# PWM_CONTROLLER.net
KiCad netlist of a schematic drawn in EasyEDA
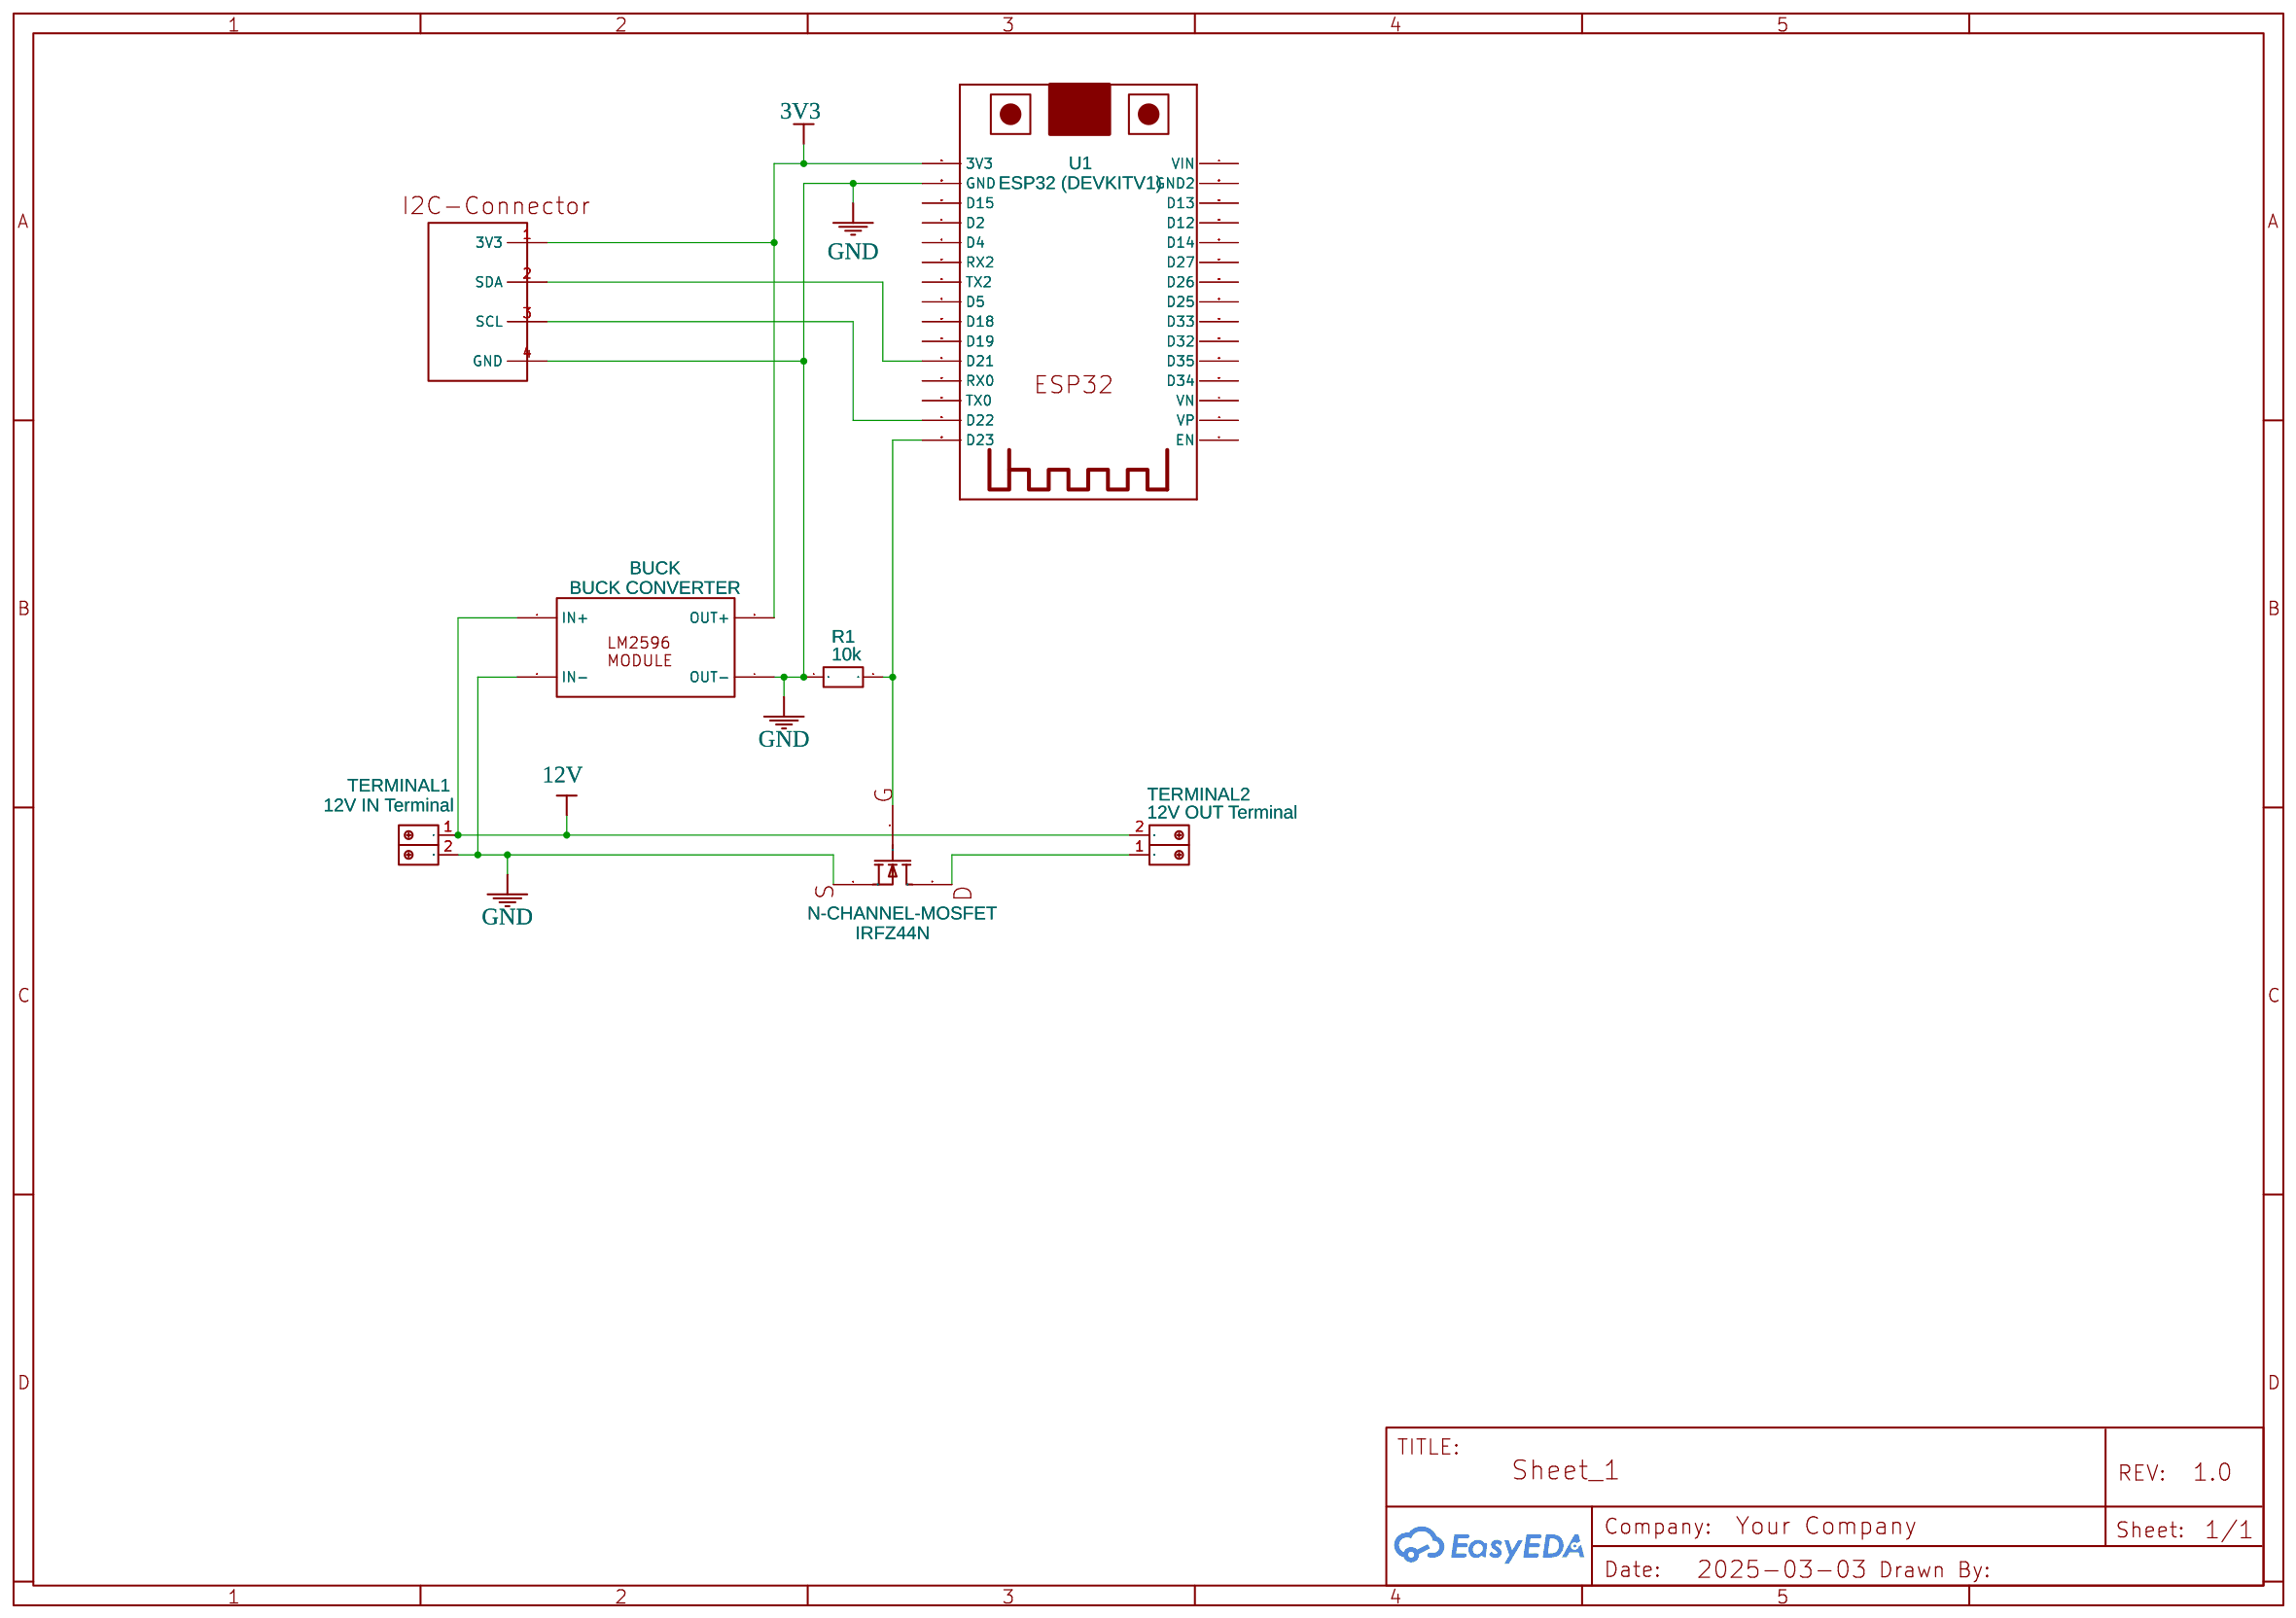
[diagram p0: schematic sheet]

(export (version "E")
  (design (tool "Eeschema 10.0.6"))
  (components
    (comp (ref "BUCK")
      (value "BUCK CONVERTER")
      (fields (field (name "Manufacturer Part") "LM2596-MODULE"))
      (libsource (lib "") (part "LM2596 MODULE - BUCK CONVERTER"))
    )
    (comp (ref "I2C-CONNECTOR") (value "I2C KEYAD (4 PIN)") (libsource (lib "") (part "I2C KEYAD (4 PIN)")))
    (comp (ref "N-CHANNEL-MOSFET") (value "IRFZ44N") (libsource (lib "") (part "MOSFET IRFZ44N")))
    (comp (ref "R1") (value "10k") (libsource (lib "") (part "R_0603_EU")))
    (comp (ref "TERMINAL1")
      (value "12V IN Terminal")
      (fields (field (name "Manufacturer Part") "Screw terminal 2p"))
      (libsource (lib "") (part "Screw terminal 2p_1"))
    )
    (comp (ref "TERMINAL2")
      (value "12V OUT Terminal")
      (fields (field (name "Manufacturer Part") "Screw terminal 2p"))
      (libsource (lib "") (part "Screw terminal 2p"))
    )
    (comp (ref "U1") (value "ESP32 (DEVKITV1)") (libsource (lib "") (part "ESP32-DEVKIT-V1-30PIN")))
  )
  (nets
    (net (code "1") (name "3V3") (class "Default")
      (node (ref "BUCK") (pin "3") (pinfunction "OUT+_3") (pintype "unspecified"))
      (node (ref "I2C-CONNECTOR") (pin "1") (pinfunction "3V3_1") (pintype "unspecified"))
      (node (ref "U1") (pin "3V3") (pinfunction "3V3_3V3") (pintype "unspecified"))
    )
    (net (code "2") (name "12V") (class "Default")
      (node (ref "BUCK") (pin "1") (pinfunction "IN+_1") (pintype "unspecified"))
      (node (ref "TERMINAL1") (pin "1") (pinfunction "1_1") (pintype "unspecified"))
      (node (ref "TERMINAL2") (pin "2") (pinfunction "2_2") (pintype "unspecified"))
    )
    (net (code "3") (name "GND") (class "Default")
      (node (ref "BUCK") (pin "2") (pinfunction "IN-_2") (pintype "unspecified"))
      (node (ref "BUCK") (pin "4") (pinfunction "OUT-_4") (pintype "unspecified"))
      (node (ref "I2C-CONNECTOR") (pin "4") (pinfunction "GND_4") (pintype "unspecified"))
      (node (ref "N-CHANNEL-MOSFET") (pin "3") (pinfunction "S_3") (pintype "unspecified"))
      (node (ref "R1") (pin "1") (pinfunction "1_1") (pintype "unspecified"))
      (node (ref "TERMINAL1") (pin "2") (pinfunction "2_2") (pintype "unspecified"))
      (node (ref "U1") (pin "GND") (pinfunction "GND_GND") (pintype "unspecified"))
    )
    (net (code "4") (name "Net-(I2C-CONNECTOR-SCL)") (class "Default")
      (node (ref "I2C-CONNECTOR") (pin "3") (pinfunction "SCL_3") (pintype "unspecified"))
      (node (ref "U1") (pin "D22") (pinfunction "D22_D22") (pintype "unspecified"))
    )
    (net (code "5") (name "Net-(I2C-CONNECTOR-SDA)") (class "Default")
      (node (ref "I2C-CONNECTOR") (pin "2") (pinfunction "SDA_2") (pintype "unspecified"))
      (node (ref "U1") (pin "D21") (pinfunction "D21_D21") (pintype "unspecified"))
    )
    (net (code "6") (name "Net-(N-CHANNEL-MOSFET-D)") (class "Default")
      (node (ref "N-CHANNEL-MOSFET") (pin "2") (pinfunction "D_2") (pintype "unspecified"))
      (node (ref "TERMINAL2") (pin "1") (pinfunction "1_1") (pintype "unspecified"))
    )
    (net (code "7") (name "Net-(N-CHANNEL-MOSFET-G)") (class "Default")
      (node (ref "N-CHANNEL-MOSFET") (pin "1") (pinfunction "G_1") (pintype "unspecified"))
      (node (ref "R1") (pin "2") (pinfunction "2_2") (pintype "unspecified"))
      (node (ref "U1") (pin "D23") (pinfunction "D23_D23") (pintype "unspecified"))
    )
    (net (code "8") (name "unconnected-(U1-PadD2)") (class "Default")
      (node (ref "U1") (pin "D2") (pinfunction "D2_D2") (pintype "unspecified"))
    )
    (net (code "9") (name "unconnected-(U1-PadD4)") (class "Default")
      (node (ref "U1") (pin "D4") (pinfunction "D4_D4") (pintype "unspecified"))
    )
    (net (code "10") (name "unconnected-(U1-PadD5)") (class "Default")
      (node (ref "U1") (pin "D5") (pinfunction "D5_D5") (pintype "unspecified"))
    )
    (net (code "11") (name "unconnected-(U1-PadD12)") (class "Default")
      (node (ref "U1") (pin "D12") (pinfunction "D12_D12") (pintype "unspecified"))
    )
    (net (code "12") (name "unconnected-(U1-PadD13)") (class "Default")
      (node (ref "U1") (pin "D13") (pinfunction "D13_D13") (pintype "unspecified"))
    )
    (net (code "13") (name "unconnected-(U1-PadD14)") (class "Default")
      (node (ref "U1") (pin "D14") (pinfunction "D14_D14") (pintype "unspecified"))
    )
    (net (code "14") (name "unconnected-(U1-PadD15)") (class "Default")
      (node (ref "U1") (pin "D15") (pinfunction "D15_D15") (pintype "unspecified"))
    )
    (net (code "15") (name "unconnected-(U1-PadD18)") (class "Default")
      (node (ref "U1") (pin "D18") (pinfunction "D18_D18") (pintype "unspecified"))
    )
    (net (code "16") (name "unconnected-(U1-PadD19)") (class "Default")
      (node (ref "U1") (pin "D19") (pinfunction "D19_D19") (pintype "unspecified"))
    )
    (net (code "17") (name "unconnected-(U1-PadD25)") (class "Default")
      (node (ref "U1") (pin "D25") (pinfunction "D25_D25") (pintype "unspecified"))
    )
    (net (code "18") (name "unconnected-(U1-PadD26)") (class "Default")
      (node (ref "U1") (pin "D26") (pinfunction "D26_D26") (pintype "unspecified"))
    )
    (net (code "19") (name "unconnected-(U1-PadD27)") (class "Default")
      (node (ref "U1") (pin "D27") (pinfunction "D27_D27") (pintype "unspecified"))
    )
    (net (code "20") (name "unconnected-(U1-PadD32)") (class "Default")
      (node (ref "U1") (pin "D32") (pinfunction "D32_D32") (pintype "unspecified"))
    )
    (net (code "21") (name "unconnected-(U1-PadD33)") (class "Default")
      (node (ref "U1") (pin "D33") (pinfunction "D33_D33") (pintype "unspecified"))
    )
    (net (code "22") (name "unconnected-(U1-PadD34)") (class "Default")
      (node (ref "U1") (pin "D34") (pinfunction "D34_D34") (pintype "unspecified"))
    )
    (net (code "23") (name "unconnected-(U1-PadD35)") (class "Default")
      (node (ref "U1") (pin "D35") (pinfunction "D35_D35") (pintype "unspecified"))
    )
    (net (code "24") (name "unconnected-(U1-PadEN)") (class "Default")
      (node (ref "U1") (pin "EN") (pinfunction "EN_EN") (pintype "unspecified"))
    )
    (net (code "25") (name "unconnected-(U1-PadGND2)") (class "Default")
      (node (ref "U1") (pin "GND2") (pinfunction "GND2_GND2") (pintype "unspecified"))
    )
    (net (code "26") (name "unconnected-(U1-PadRX0)") (class "Default")
      (node (ref "U1") (pin "RX0") (pinfunction "RX0_RX0") (pintype "unspecified"))
    )
    (net (code "27") (name "unconnected-(U1-PadRX2)") (class "Default")
      (node (ref "U1") (pin "RX2") (pinfunction "RX2_RX2") (pintype "unspecified"))
    )
    (net (code "28") (name "unconnected-(U1-PadTX0)") (class "Default")
      (node (ref "U1") (pin "TX0") (pinfunction "TX0_TX0") (pintype "unspecified"))
    )
    (net (code "29") (name "unconnected-(U1-PadTX2)") (class "Default")
      (node (ref "U1") (pin "TX2") (pinfunction "TX2_TX2") (pintype "unspecified"))
    )
    (net (code "30") (name "unconnected-(U1-PadVIN)") (class "Default")
      (node (ref "U1") (pin "VIN") (pinfunction "VIN_VIN") (pintype "unspecified"))
    )
    (net (code "31") (name "unconnected-(U1-PadVN)") (class "Default")
      (node (ref "U1") (pin "VN") (pinfunction "VN_VN") (pintype "unspecified"))
    )
    (net (code "32") (name "unconnected-(U1-PadVP)") (class "Default")
      (node (ref "U1") (pin "VP") (pinfunction "VP_VP") (pintype "unspecified"))
    )
  )
)
